# PI_HAT.net
KiCad netlist of a schematic drawn in EAGLE
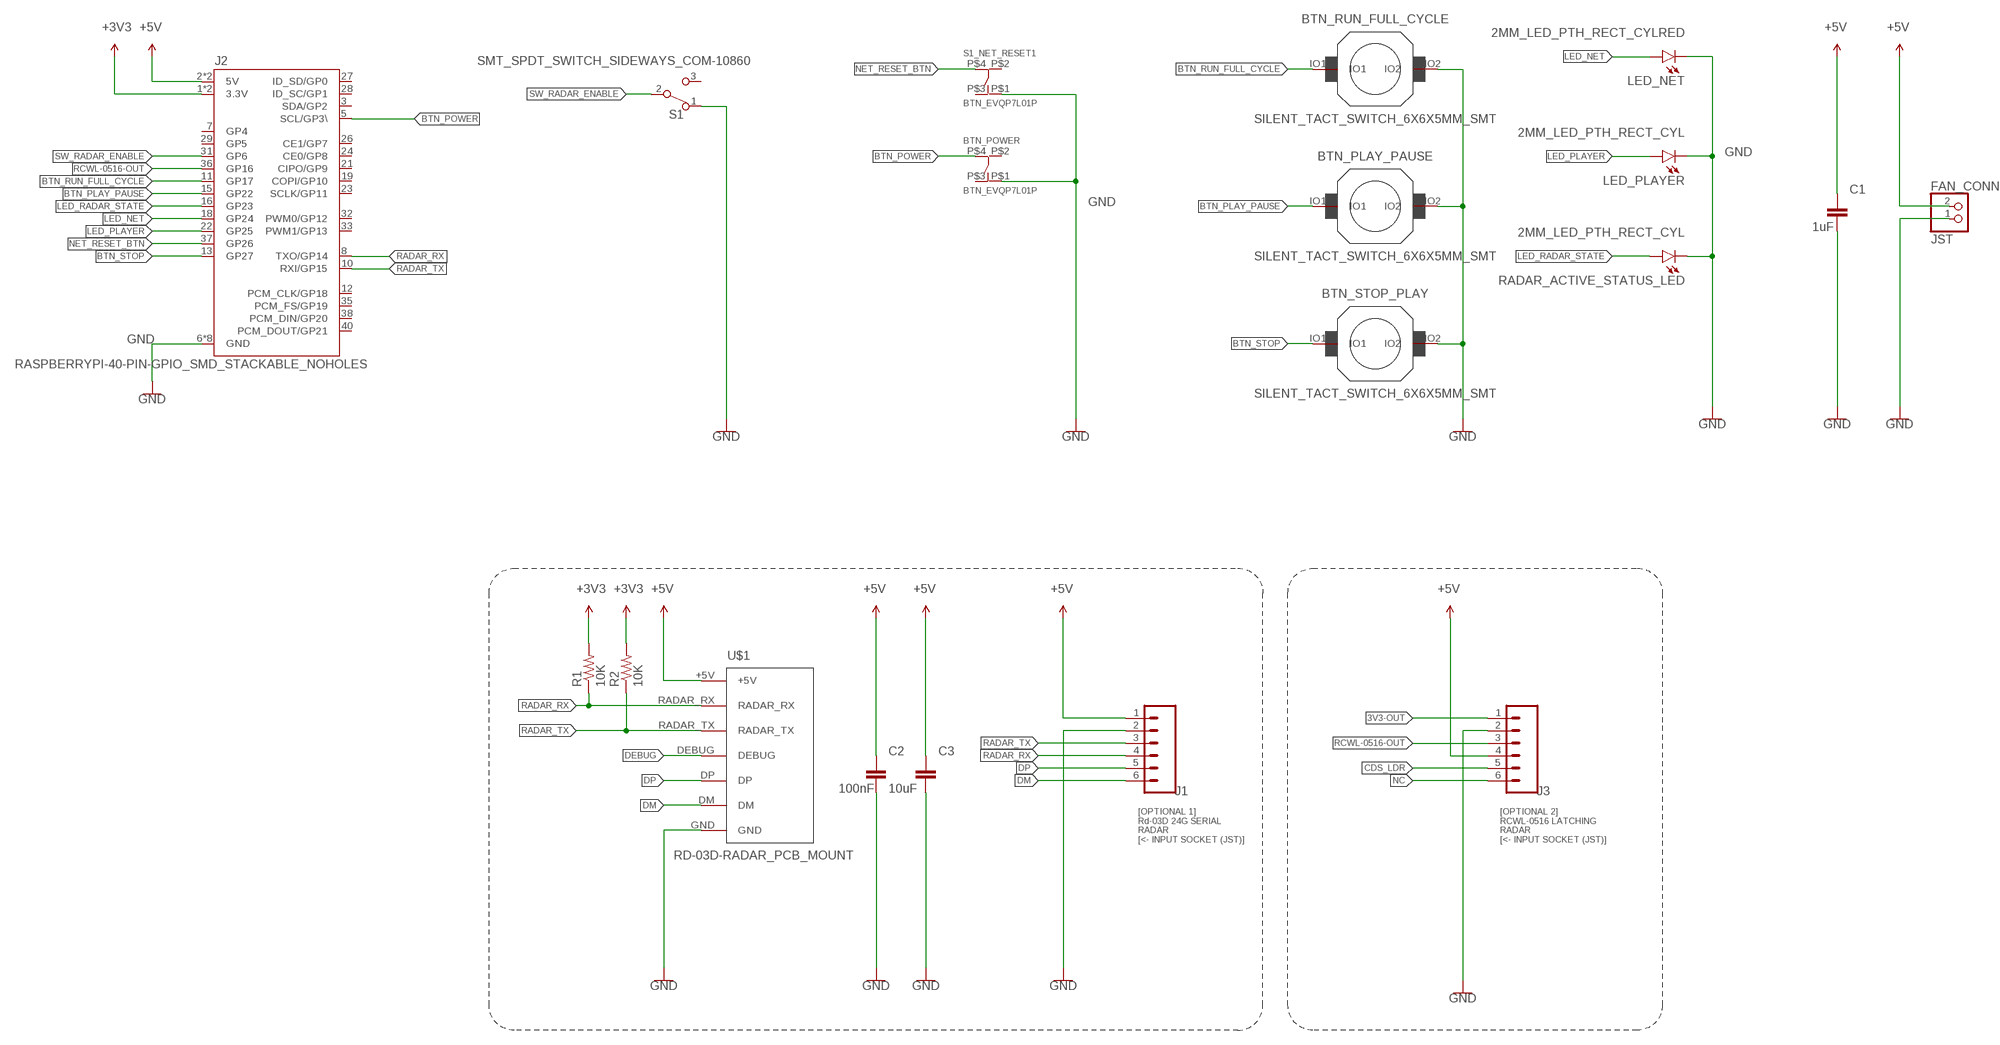
[diagram p0: schematic, sheet 1]

(export (version "E")
  (design (tool "Eeschema 10.0.6"))
  (components
    (comp (ref "BTN_PLAY_PAUSE")
      (value "SILENT_TACT_SWITCH_6X6X5MM_SMT")
      (footprint "eagle-import:SILENT_TACT_SWITCH_6X6X5MM_SMT")
      (libsource (lib "eagle-import") (part "SILENT_TACT_SWITCH_6X6X5MM_SMT"))
    )
    (comp (ref "BTN_POWER")
      (value "BTN_EVQP7L01P")
      (footprint "eagle-import:BTN_EVQP7L01P")
      (libsource (lib "eagle-import") (part "BTN_EVQP7L01P"))
    )
    (comp (ref "BTN_RUN_FULL_CYCLE")
      (value "SILENT_TACT_SWITCH_6X6X5MM_SMT")
      (footprint "eagle-import:SILENT_TACT_SWITCH_6X6X5MM_SMT")
      (libsource (lib "eagle-import") (part "SILENT_TACT_SWITCH_6X6X5MM_SMT"))
    )
    (comp (ref "BTN_STOP_PLAY")
      (value "SILENT_TACT_SWITCH_6X6X5MM_SMT")
      (footprint "eagle-import:SILENT_TACT_SWITCH_6X6X5MM_SMT")
      (libsource (lib "eagle-import") (part "SILENT_TACT_SWITCH_6X6X5MM_SMT"))
    )
    (comp (ref "C1")
      (value "1uF")
      (footprint "eagle-import:CAPC2012X110")
      (libsource (lib "eagle-import") (part "CAPACITORSCHIP-0805(2012-METRIC)_"))
    )
    (comp (ref "C2")
      (value "100nF")
      (footprint "eagle-import:CAPC2012X110")
      (libsource (lib "eagle-import") (part "CAPACITORSCHIP-0805(2012-METRIC)_"))
    )
    (comp (ref "C3")
      (value "10uF")
      (footprint "eagle-import:CAPC2012X110")
      (libsource (lib "eagle-import") (part "CAPACITORSCHIP-0805(2012-METRIC)_"))
    )
    (comp (ref "FAN_CONN")
      (value "JST")
      (footprint "eagle-import:JST_2.5MM_SMT")
      (libsource (lib "eagle-import") (part "ADAFRUIT_JST_2PIN-SMT-RA"))
    )
    (comp (ref "J1")
      (value "JST_6PIN_1MMSMD-1MM")
      (footprint "eagle-import:JST_6PIN_1MM")
      (libsource (lib "eagle-import") (part "JST_6PIN_1MMSMD-1MM"))
    )
    (comp (ref "J2")
      (value "RASPBERRYPI-40-PIN-GPIO_SMD_STACKABLE_NOHOLES")
      (footprint "eagle-import:RASPBERRY_PI_HAT_40_PIN_PTH_WITH_REFERNCE")
      (libsource (lib "eagle-import") (part "RASPBERRYPI-40-PIN-GPIO_PTH_REFERENCE"))
    )
    (comp (ref "J3")
      (value "JST_6PIN_1MMSMD-1MM")
      (footprint "eagle-import:JST_6PIN_1MM")
      (libsource (lib "eagle-import") (part "JST_6PIN_1MMSMD-1MM"))
    )
    (comp (ref "LED_NET")
      (value "2MM_LED_PTH_RECT_CYLRED")
      (footprint "eagle-import:2MM_LED_PTH_RECT_CYL_RED")
      (libsource (lib "eagle-import") (part "2MM_LED_PTH_RECT_CYLRED"))
    )
    (comp (ref "LED_PLAYER")
      (value "2MM_LED_PTH_RECT_CYL")
      (footprint "eagle-import:2MM_LED_PTH_RECT_CYL_YELLOW")
      (libsource (lib "eagle-import") (part "2MM_LED_PTH_RECT_CYL"))
    )
    (comp (ref "R1")
      (value "10K")
      (footprint "eagle-import:RESC1608X60")
      (libsource (lib "eagle-import") (part "R-USCHIP-0603(1608-METRIC)_"))
    )
    (comp (ref "R2")
      (value "10K")
      (footprint "eagle-import:RESC1608X60")
      (libsource (lib "eagle-import") (part "R-USCHIP-0603(1608-METRIC)_"))
    )
    (comp (ref "RADAR_ACTIVE_STATUS_LED")
      (value "2MM_LED_PTH_RECT_CYL")
      (footprint "eagle-import:2MM_LED_PTH_RECT_CYL_YELLOW")
      (libsource (lib "eagle-import") (part "2MM_LED_PTH_RECT_CYL"))
    )
    (comp (ref "S1")
      (value "SMT_SPDT_SWITCH_SIDEWAYS_COM-10860")
      (footprint "eagle-import:SMT_SPDT_SWITCH_SIDEWAYS")
      (fields (field (name "MANUFACTURER") "SparkFun Electronics") (field (name "MPN") "10860"))
      (libsource (lib "eagle-import") (part "SMT_SPDT_SWITCH_SIDEWAYS_COM-10860"))
    )
    (comp (ref "S1_NET_RESET1")
      (value "BTN_EVQP7L01P")
      (footprint "eagle-import:BTN_EVQP7L01P")
      (libsource (lib "eagle-import") (part "BTN_EVQP7L01P"))
    )
    (comp (ref "U$1")
      (value "RD-03D-RADAR_PCB_MOUNT")
      (footprint "eagle-import:RD-03D-RADAR_PCB_MOUNT")
      (libsource (lib "eagle-import") (part "RD-03D-RADAR_PCB_MOUNT"))
    )
  )
  (nets
    (net (code "1") (name "+3V3") (class "Default")
      (node (ref "J2") (pin "1") (pinfunction "3.3V_1") (pintype "power_in"))
      (node (ref "J2") (pin "17") (pinfunction "3.3V_17") (pintype "power_in"))
      (node (ref "R1") (pin "2") (pinfunction "2_2") (pintype "passive"))
      (node (ref "R2") (pin "2") (pinfunction "2_2") (pintype "passive"))
    )
    (net (code "2") (name "+5V") (class "Default")
      (node (ref "C1") (pin "1") (pinfunction "1_1") (pintype "passive"))
      (node (ref "C2") (pin "1") (pinfunction "1_1") (pintype "passive"))
      (node (ref "C3") (pin "1") (pinfunction "1_1") (pintype "passive"))
      (node (ref "FAN_CONN") (pin "2") (pinfunction "1_2") (pintype "passive"))
      (node (ref "J1") (pin "1") (pinfunction "1_1") (pintype "passive"))
      (node (ref "J2") (pin "2") (pinfunction "5V_2") (pintype "power_in"))
      (node (ref "J2") (pin "4") (pinfunction "5V_4") (pintype "power_in"))
      (node (ref "J3") (pin "4") (pinfunction "4_4") (pintype "passive"))
      (node (ref "U$1") (pin "+5V") (pinfunction "+5V_+5V") (pintype "bidirectional"))
    )
    (net (code "3") (name "3V3-OUT") (class "Default")
      (node (ref "J3") (pin "1") (pinfunction "1_1") (pintype "passive"))
    )
    (net (code "4") (name "BTN_PLAY_PAUSE") (class "Default")
      (node (ref "BTN_PLAY_PAUSE") (pin "IO1") (pinfunction "IO1_IO1") (pintype "bidirectional"))
      (node (ref "J2") (pin "15") (pinfunction "GP22_15") (pintype "bidirectional"))
    )
    (net (code "5") (name "BTN_POWER") (class "Default")
      (node (ref "BTN_POWER") (pin "P$4") (pinfunction "P$4_P$4") (pintype "bidirectional"))
      (node (ref "J2") (pin "5") (pinfunction "SCL/GP3\\_5") (pintype "bidirectional"))
    )
    (net (code "6") (name "BTN_RUN_FULL_CYCLE") (class "Default")
      (node (ref "BTN_RUN_FULL_CYCLE") (pin "IO1") (pinfunction "IO1_IO1") (pintype "bidirectional"))
      (node (ref "J2") (pin "11") (pinfunction "GP17_11") (pintype "bidirectional"))
    )
    (net (code "7") (name "BTN_STOP") (class "Default")
      (node (ref "BTN_STOP_PLAY") (pin "IO1") (pinfunction "IO1_IO1") (pintype "bidirectional"))
      (node (ref "J2") (pin "13") (pinfunction "GP27_13") (pintype "bidirectional"))
    )
    (net (code "8") (name "CDS_LDR") (class "Default")
      (node (ref "J3") (pin "5") (pinfunction "5_5") (pintype "passive"))
    )
    (net (code "9") (name "DEBUG") (class "Default")
      (node (ref "U$1") (pin "DEBUG") (pinfunction "DEBUG_DEBUG") (pintype "bidirectional"))
    )
    (net (code "10") (name "DM") (class "Default")
      (node (ref "J1") (pin "6") (pinfunction "6_6") (pintype "passive"))
      (node (ref "U$1") (pin "DM") (pinfunction "DM_DM") (pintype "bidirectional"))
    )
    (net (code "11") (name "DP") (class "Default")
      (node (ref "J1") (pin "5") (pinfunction "5_5") (pintype "passive"))
      (node (ref "U$1") (pin "DP") (pinfunction "DP_DP") (pintype "bidirectional"))
    )
    (net (code "12") (name "GND") (class "Default")
      (node (ref "BTN_PLAY_PAUSE") (pin "IO2") (pinfunction "IO2_IO2") (pintype "bidirectional"))
      (node (ref "BTN_POWER") (pin "P$1") (pinfunction "1_P$1") (pintype "bidirectional"))
      (node (ref "BTN_RUN_FULL_CYCLE") (pin "IO2") (pinfunction "IO2_IO2") (pintype "bidirectional"))
      (node (ref "BTN_STOP_PLAY") (pin "IO2") (pinfunction "IO2_IO2") (pintype "bidirectional"))
      (node (ref "C1") (pin "2") (pinfunction "2_2") (pintype "passive"))
      (node (ref "C2") (pin "2") (pinfunction "2_2") (pintype "passive"))
      (node (ref "C3") (pin "2") (pinfunction "2_2") (pintype "passive"))
      (node (ref "FAN_CONN") (pin "1") (pinfunction "2_1") (pintype "passive"))
      (node (ref "J1") (pin "2") (pinfunction "2_2") (pintype "passive"))
      (node (ref "J2") (pin "14") (pinfunction "GND_14") (pintype "power_in"))
      (node (ref "J2") (pin "20") (pinfunction "GND_20") (pintype "power_in"))
      (node (ref "J2") (pin "25") (pinfunction "GND_25") (pintype "power_in"))
      (node (ref "J2") (pin "30") (pinfunction "GND_30") (pintype "power_in"))
      (node (ref "J2") (pin "34") (pinfunction "GND_34") (pintype "power_in"))
      (node (ref "J2") (pin "39") (pinfunction "GND_39") (pintype "power_in"))
      (node (ref "J2") (pin "6") (pinfunction "GND_6") (pintype "power_in"))
      (node (ref "J2") (pin "9") (pinfunction "GND_9") (pintype "power_in"))
      (node (ref "J3") (pin "2") (pinfunction "2_2") (pintype "passive"))
      (node (ref "LED_NET") (pin "K") (pinfunction "CATHODE_K") (pintype "passive"))
      (node (ref "LED_PLAYER") (pin "K") (pinfunction "CATHODE_K") (pintype "passive"))
      (node (ref "RADAR_ACTIVE_STATUS_LED") (pin "K") (pinfunction "CATHODE_K") (pintype "passive"))
      (node (ref "S1") (pin "1") (pinfunction "NC_1") (pintype "passive"))
      (node (ref "S1_NET_RESET1") (pin "P$1") (pinfunction "1_P$1") (pintype "bidirectional"))
      (node (ref "U$1") (pin "GND") (pinfunction "GND_GND") (pintype "bidirectional"))
    )
    (net (code "13") (name "LED_NET") (class "Default")
      (node (ref "J2") (pin "18") (pinfunction "GP24_18") (pintype "bidirectional"))
      (node (ref "LED_NET") (pin "A") (pinfunction "ANODE_A") (pintype "passive"))
    )
    (net (code "14") (name "LED_PLAYER") (class "Default")
      (node (ref "J2") (pin "22") (pinfunction "GP25_22") (pintype "bidirectional"))
      (node (ref "LED_PLAYER") (pin "A") (pinfunction "ANODE_A") (pintype "passive"))
    )
    (net (code "15") (name "LED_RADAR_STATE") (class "Default")
      (node (ref "J2") (pin "16") (pinfunction "GP23_16") (pintype "bidirectional"))
      (node (ref "RADAR_ACTIVE_STATUS_LED") (pin "A") (pinfunction "ANODE_A") (pintype "passive"))
    )
    (net (code "16") (name "NC") (class "Default")
      (node (ref "J3") (pin "6") (pinfunction "6_6") (pintype "passive"))
    )
    (net (code "17") (name "NET_RESET_BTN") (class "Default")
      (node (ref "J2") (pin "37") (pinfunction "GP26_37") (pintype "bidirectional"))
      (node (ref "S1_NET_RESET1") (pin "P$4") (pinfunction "P$4_P$4") (pintype "bidirectional"))
    )
    (net (code "18") (name "RADAR_RX") (class "Default")
      (node (ref "J1") (pin "4") (pinfunction "4_4") (pintype "passive"))
      (node (ref "J2") (pin "8") (pinfunction "TXO/GP14_8") (pintype "output"))
      (node (ref "R1") (pin "1") (pinfunction "1_1") (pintype "passive"))
      (node (ref "U$1") (pin "RADAR_RX") (pinfunction "RADAR_RX_RADAR_RX") (pintype "bidirectional"))
    )
    (net (code "19") (name "RADAR_TX") (class "Default")
      (node (ref "J1") (pin "3") (pinfunction "3_3") (pintype "passive"))
      (node (ref "J2") (pin "10") (pinfunction "RXI/GP15_10") (pintype "input"))
      (node (ref "R2") (pin "1") (pinfunction "1_1") (pintype "passive"))
      (node (ref "U$1") (pin "RADAR_TX") (pinfunction "RADAR_TX_RADAR_TX") (pintype "bidirectional"))
    )
    (net (code "20") (name "RCWL-0516-OUT") (class "Default")
      (node (ref "J2") (pin "36") (pinfunction "GP16_36") (pintype "bidirectional"))
      (node (ref "J3") (pin "3") (pinfunction "3_3") (pintype "passive"))
    )
    (net (code "21") (name "SW_RADAR_ENABLE") (class "Default")
      (node (ref "J2") (pin "31") (pinfunction "GP6_31") (pintype "bidirectional"))
      (node (ref "S1") (pin "2") (pinfunction "COM_2") (pintype "passive"))
    )
    (net (code "22") (name "unconnected-(BTN_POWER-PadP$2)") (class "Default")
      (node (ref "BTN_POWER") (pin "P$2") (pinfunction "P$2_P$2") (pintype "bidirectional"))
    )
    (net (code "23") (name "unconnected-(BTN_POWER-PadP$3)") (class "Default")
      (node (ref "BTN_POWER") (pin "P$3") (pinfunction "P$3_P$3") (pintype "bidirectional"))
    )
    (net (code "24") (name "unconnected-(J2-CE0{slash}GP8-Pad24)") (class "Default")
      (node (ref "J2") (pin "24") (pinfunction "CE0/GP8_24") (pintype "output"))
    )
    (net (code "25") (name "unconnected-(J2-CE1{slash}GP7-Pad26)") (class "Default")
      (node (ref "J2") (pin "26") (pinfunction "CE1/GP7_26") (pintype "output"))
    )
    (net (code "26") (name "unconnected-(J2-CIPO{slash}GP9-Pad21)") (class "Default")
      (node (ref "J2") (pin "21") (pinfunction "CIPO/GP9_21") (pintype "input"))
    )
    (net (code "27") (name "unconnected-(J2-COPI{slash}GP10-Pad19)") (class "Default")
      (node (ref "J2") (pin "19") (pinfunction "COPI/GP10_19") (pintype "output"))
    )
    (net (code "28") (name "unconnected-(J2-GP4-Pad7)") (class "Default")
      (node (ref "J2") (pin "7") (pinfunction "GP4_7") (pintype "bidirectional"))
    )
    (net (code "29") (name "unconnected-(J2-GP5-Pad29)") (class "Default")
      (node (ref "J2") (pin "29") (pinfunction "GP5_29") (pintype "bidirectional"))
    )
    (net (code "30") (name "unconnected-(J2-ID_SC{slash}GP1-Pad28)") (class "Default")
      (node (ref "J2") (pin "28") (pinfunction "ID_SC/GP1_28") (pintype "bidirectional"))
    )
    (net (code "31") (name "unconnected-(J2-ID_SD{slash}GP0-Pad27)") (class "Default")
      (node (ref "J2") (pin "27") (pinfunction "ID_SD/GP0_27") (pintype "bidirectional"))
    )
    (net (code "32") (name "unconnected-(J2-PCM_CLK{slash}GP18-Pad12)") (class "Default")
      (node (ref "J2") (pin "12") (pinfunction "PCM_CLK/GP18_12") (pintype "bidirectional"))
    )
    (net (code "33") (name "unconnected-(J2-PCM_DIN{slash}GP20-Pad38)") (class "Default")
      (node (ref "J2") (pin "38") (pinfunction "PCM_DIN/GP20_38") (pintype "bidirectional"))
    )
    (net (code "34") (name "unconnected-(J2-PCM_DOUT{slash}GP21-Pad40)") (class "Default")
      (node (ref "J2") (pin "40") (pinfunction "PCM_DOUT/GP21_40") (pintype "bidirectional"))
    )
    (net (code "35") (name "unconnected-(J2-PCM_FS{slash}GP19-Pad35)") (class "Default")
      (node (ref "J2") (pin "35") (pinfunction "PCM_FS/GP19_35") (pintype "bidirectional"))
    )
    (net (code "36") (name "unconnected-(J2-PWM0{slash}GP12-Pad32)") (class "Default")
      (node (ref "J2") (pin "32") (pinfunction "PWM0/GP12_32") (pintype "bidirectional"))
    )
    (net (code "37") (name "unconnected-(J2-PWM1{slash}GP13-Pad33)") (class "Default")
      (node (ref "J2") (pin "33") (pinfunction "PWM1/GP13_33") (pintype "bidirectional"))
    )
    (net (code "38") (name "unconnected-(J2-SCLK{slash}GP11-Pad23)") (class "Default")
      (node (ref "J2") (pin "23") (pinfunction "SCLK/GP11_23") (pintype "output"))
    )
    (net (code "39") (name "unconnected-(J2-SDA{slash}GP2-Pad3)") (class "Default")
      (node (ref "J2") (pin "3") (pinfunction "SDA/GP2_3") (pintype "bidirectional"))
    )
    (net (code "40") (name "unconnected-(S1-NO-Pad3)") (class "Default")
      (node (ref "S1") (pin "3") (pinfunction "NO_3") (pintype "passive"))
    )
    (net (code "41") (name "unconnected-(S1_NET_RESET1-PadP$2)") (class "Default")
      (node (ref "S1_NET_RESET1") (pin "P$2") (pinfunction "P$2_P$2") (pintype "bidirectional"))
    )
    (net (code "42") (name "unconnected-(S1_NET_RESET1-PadP$3)") (class "Default")
      (node (ref "S1_NET_RESET1") (pin "P$3") (pinfunction "P$3_P$3") (pintype "bidirectional"))
    )
  )
)
